# Enclosure_130x95_BPM-R.net
KiCad netlist of a schematic drawn in EAGLE
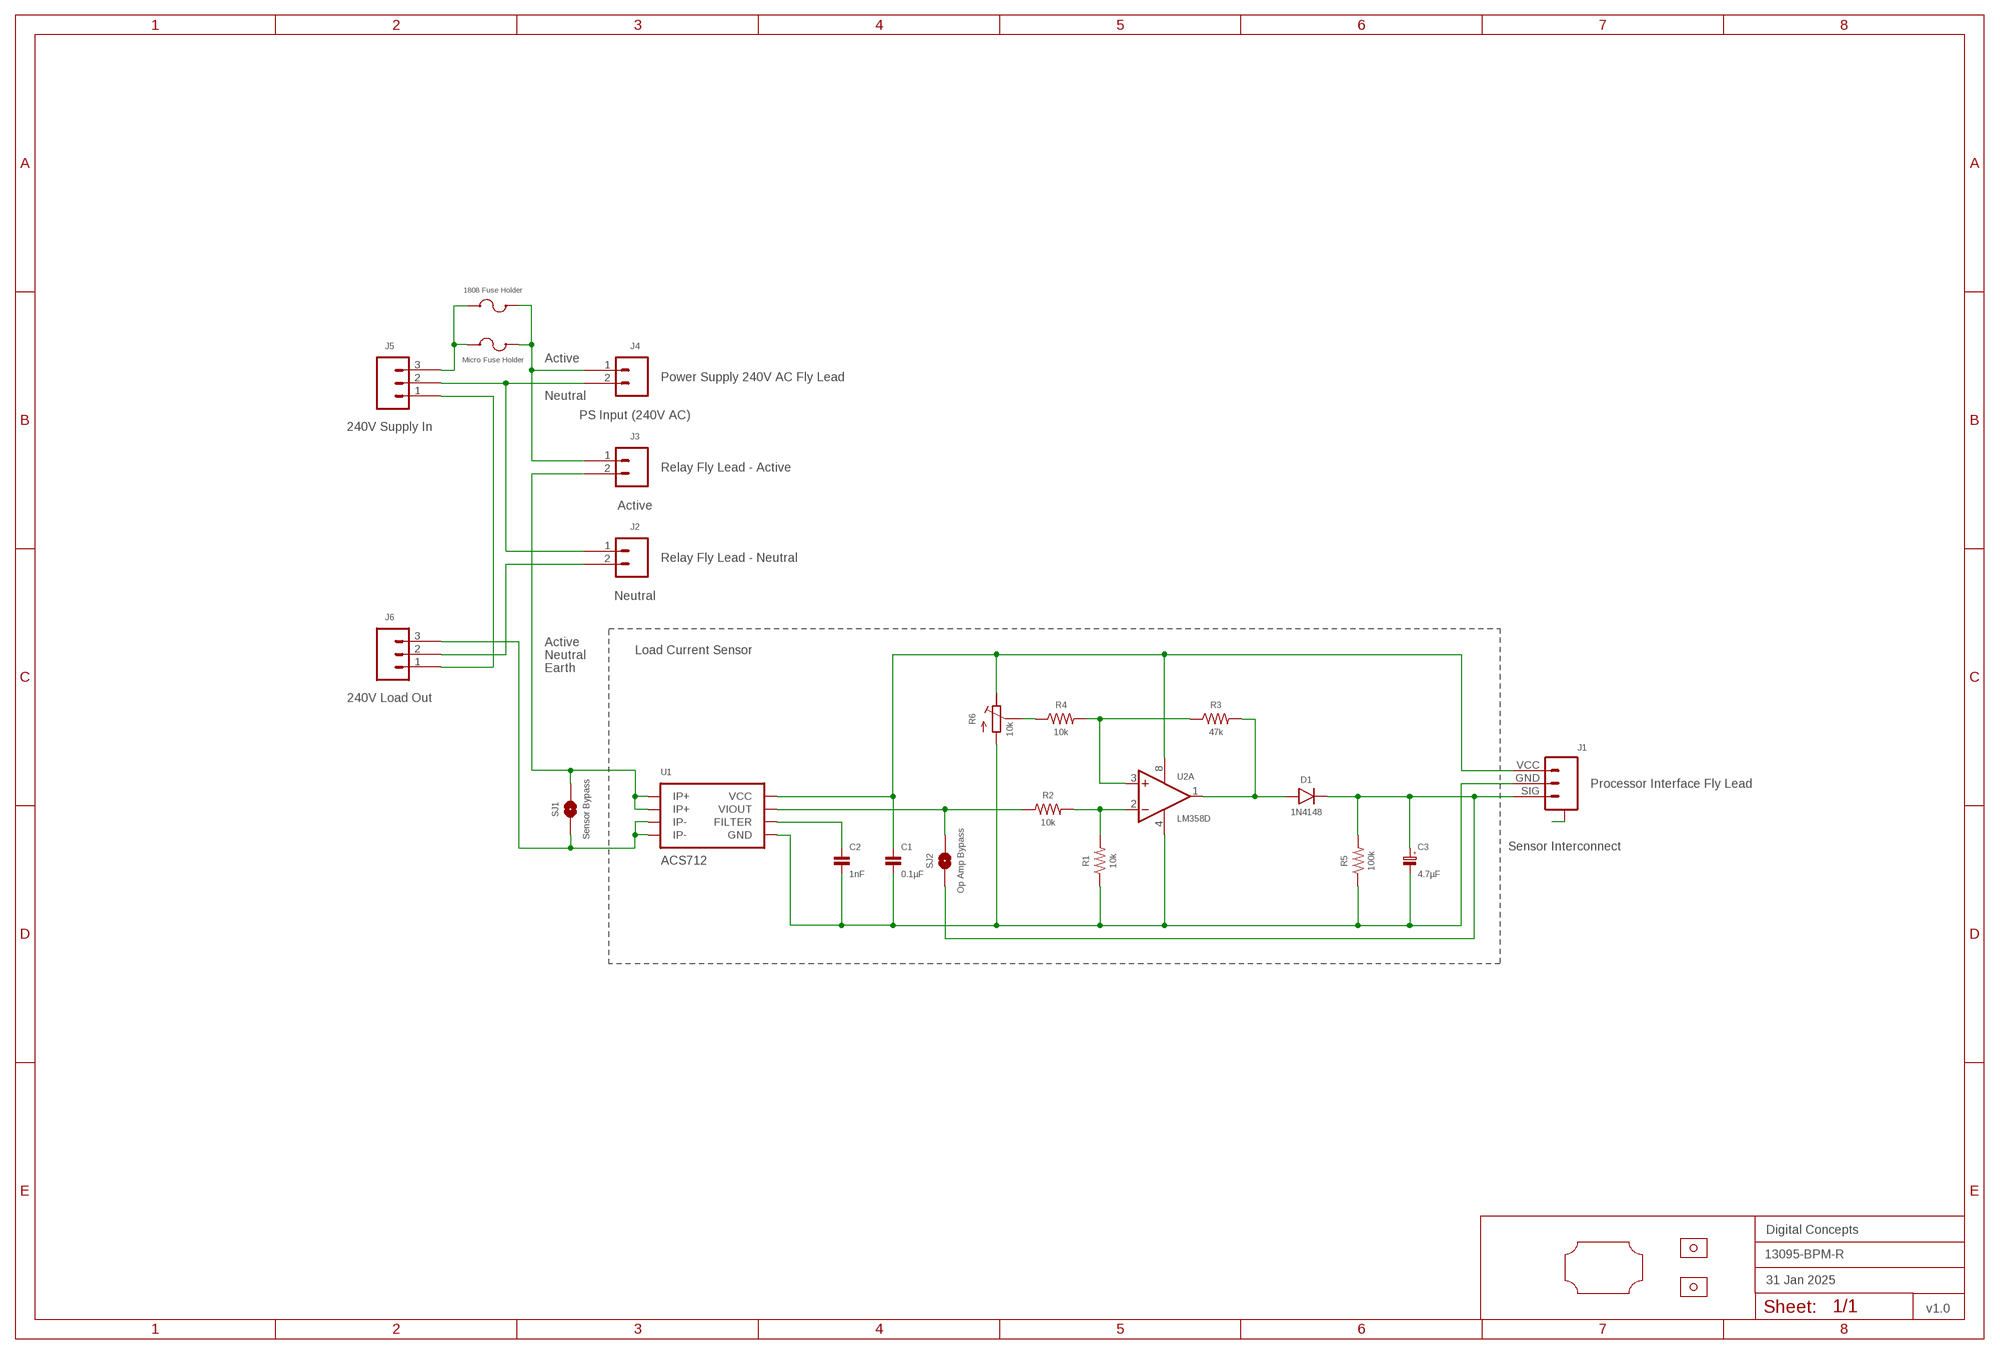
[diagram p0: schematic, sheet 1]

(export (version "E")
  (design (tool "Eeschema 10.0.6"))
  (components
    (comp (ref "C1")
      (value "0.1µF")
      (footprint "eagle-import:C0805")
      (libsource (lib "eagle-import") (part "CAPACITOR-0805"))
    )
    (comp (ref "C2")
      (value "1nF")
      (footprint "eagle-import:C0805")
      (libsource (lib "eagle-import") (part "CAPACITOR-0805"))
    )
    (comp (ref "C3")
      (value "4.7µF")
      (footprint "eagle-import:C1206-POLARISED")
      (libsource (lib "eagle-import") (part "CAPACITOR-1206-TANTALUM"))
    )
    (comp (ref "D1")
      (value "1N4148")
      (footprint "eagle-import:SOD-323")
      (libsource (lib "eagle-import") (part "DIODE-1N4148-SOD323"))
    )
    (comp (ref "F2")
      (value "1808 Fuse Holder")
      (footprint "eagle-import:FUSE-HOLDER-1808")
      (libsource (lib "eagle-import") (part "FUSE-HOLDER-1808"))
    )
    (comp (ref "J1")
      (value "Sensor Interconnect")
      (footprint "eagle-import:JST-SH1.0-3-HORIZONTAL-SIG")
      (libsource (lib "eagle-import") (part "JST-SH1.0-3-SMD-HORIZONTAL-SIG"))
    )
    (comp (ref "J2")
      (value "Neutral")
      (footprint "eagle-import:TERMINAL-SCREW-2P")
      (libsource (lib "eagle-import") (part "TERMINAL_SCREW_2P_VERTICAL"))
    )
    (comp (ref "J3")
      (value "Active")
      (footprint "eagle-import:TERMINAL-SCREW-2P")
      (libsource (lib "eagle-import") (part "TERMINAL_SCREW_2P_VERTICAL"))
    )
    (comp (ref "J4")
      (value "PS Input (240V AC)")
      (footprint "eagle-import:JST-XH2.4-2-HORIZONTAL")
      (libsource (lib "eagle-import") (part "JST-XH2.54-2-HORIZONTAL"))
    )
    (comp (ref "J5")
      (value "240V Supply In")
      (footprint "eagle-import:TERMINAL-SCREW-3P")
      (libsource (lib "eagle-import") (part "TERMINAL_SCREW_3P_VERTICAL"))
    )
    (comp (ref "J6")
      (value "240V Load Out")
      (footprint "eagle-import:TERMINAL-SCREW-3P")
      (libsource (lib "eagle-import") (part "TERMINAL_SCREW_3P_VERTICAL"))
    )
    (comp (ref "R1")
      (value "10k")
      (footprint "eagle-import:R0805")
      (libsource (lib "eagle-import") (part "RESISTORR0805"))
    )
    (comp (ref "R2")
      (value "10k")
      (footprint "eagle-import:R0805")
      (libsource (lib "eagle-import") (part "RESISTORR0805"))
    )
    (comp (ref "R3")
      (value "47k")
      (footprint "eagle-import:R0805")
      (libsource (lib "eagle-import") (part "RESISTORR0805"))
    )
    (comp (ref "R4")
      (value "10k")
      (footprint "eagle-import:R0805")
      (libsource (lib "eagle-import") (part "RESISTORR0805"))
    )
    (comp (ref "R5")
      (value "100k")
      (footprint "eagle-import:R0805")
      (libsource (lib "eagle-import") (part "RESISTORR0805"))
    )
    (comp (ref "R6")
      (value "10k")
      (footprint "eagle-import:RTRIM3386P")
      (libsource (lib "eagle-import") (part "RESISTOR-TRIMM-3386P"))
    )
    (comp (ref "SJ1")
      (value "Sensor Bypass")
      (footprint "eagle-import:SJ")
      (libsource (lib "eagle-import") (part "SJ"))
    )
    (comp (ref "SJ2")
      (value "Op Amp Bypass")
      (footprint "eagle-import:SJ")
      (libsource (lib "eagle-import") (part "SJ"))
    )
    (comp (ref "U$1")
      (value "PCB-OUTLINE-130X95-MAX-RC-H3")
      (footprint "eagle-import:PROTO-130X95-OUTLINE-MAX-RC-H3")
      (libsource (lib "eagle-import") (part "PCB-OUTLINE-130X95-MAX-RC-H3"))
    )
    (comp (ref "U$2")
      (value "Micro Fuse Holder")
      (footprint "eagle-import:FUSE-HOLDER-MICRO")
      (libsource (lib "eagle-import") (part "FUSE-HOLDER"))
    )
    (comp (ref "U$4")
      (value "STRAIN-RELIEF-SADDLE")
      (footprint "eagle-import:STRAIN-RELIEF-SADDLE")
      (libsource (lib "eagle-import") (part "STRAIN-RELIEF-SADDLE"))
    )
    (comp (ref "U$5")
      (value "STRAIN-RELIEF-SADDLE")
      (footprint "eagle-import:STRAIN-RELIEF-SADDLE")
      (libsource (lib "eagle-import") (part "STRAIN-RELIEF-SADDLE"))
    )
    (comp (ref "U1")
      (value "ACS712")
      (footprint "eagle-import:SOP-8")
      (libsource (lib "eagle-import") (part "ACS712"))
    )
    (comp (ref "U2")
      (value "LM358D")
      (footprint "eagle-import:SOP-8")
      (libsource (lib "eagle-import") (part "LM358D"))
    )
  )
  (nets
    (net (code "1") (name "Net-(C3-+)") (class "Default")
      (node (ref "C3") (pin "1") (pinfunction "+_1") (pintype "passive"))
      (node (ref "D1") (pin "C") (pinfunction "1_C") (pintype "bidirectional"))
      (node (ref "J1") (pin "SIG") (pinfunction "1_SIG") (pintype "passive"))
      (node (ref "R5") (pin "2") (pinfunction "2_2") (pintype "passive"))
      (node (ref "SJ2") (pin "1") (pinfunction "1_1") (pintype "passive"))
    )
    (net (code "2") (name "Net-(C3--)") (class "Default")
      (node (ref "C1") (pin "2") (pinfunction "2_2") (pintype "passive"))
      (node (ref "C2") (pin "2") (pinfunction "2_2") (pintype "passive"))
      (node (ref "C3") (pin "2") (pinfunction "-_2") (pintype "passive"))
      (node (ref "J1") (pin "GND") (pinfunction "2_GND") (pintype "passive"))
      (node (ref "R1") (pin "1") (pinfunction "1_1") (pintype "passive"))
      (node (ref "R5") (pin "1") (pinfunction "1_1") (pintype "passive"))
      (node (ref "R6") (pin "3") (pinfunction "A_3") (pintype "passive"))
      (node (ref "U1") (pin "5") (pinfunction "GND_5") (pintype "power_in"))
      (node (ref "U2") (pin "4") (pinfunction "V-_4") (pintype "power_in"))
    )
    (net (code "3") (name "Net-(D1-2)") (class "Default")
      (node (ref "D1") (pin "A") (pinfunction "2_A") (pintype "bidirectional"))
      (node (ref "R3") (pin "2") (pinfunction "2_2") (pintype "passive"))
      (node (ref "U2") (pin "1") (pinfunction "OUT_1") (pintype "output"))
    )
    (net (code "4") (name "Net-(F2-1)") (class "Default")
      (node (ref "F2") (pin "P$1") (pinfunction "1_P$1") (pintype "passive"))
      (node (ref "J5") (pin "3") (pinfunction "3_3") (pintype "passive"))
      (node (ref "U$2") (pin "P$1") (pinfunction "1_P$1") (pintype "passive"))
      (node (ref "U$2") (pin "P$2") (pinfunction "1_P$2") (pintype "passive"))
    )
    (net (code "5") (name "Net-(F2-2)") (class "Default")
      (node (ref "F2") (pin "P$2") (pinfunction "2_P$2") (pintype "passive"))
      (node (ref "J3") (pin "1") (pinfunction "1_1") (pintype "passive"))
      (node (ref "J4") (pin "1") (pinfunction "1_1") (pintype "passive"))
      (node (ref "U$2") (pin "P$3") (pinfunction "2_P$3") (pintype "passive"))
      (node (ref "U$2") (pin "P$4") (pinfunction "2_P$4") (pintype "passive"))
    )
    (net (code "6") (name "Net-(J1-3)") (class "Default")
      (node (ref "C1") (pin "1") (pinfunction "1_1") (pintype "passive"))
      (node (ref "J1") (pin "VCC") (pinfunction "3_VCC") (pintype "passive"))
      (node (ref "R6") (pin "1") (pinfunction "E_1") (pintype "passive"))
      (node (ref "U1") (pin "8") (pinfunction "VCC_8") (pintype "power_in"))
      (node (ref "U2") (pin "8") (pinfunction "V+_8") (pintype "power_in"))
    )
    (net (code "7") (name "Net-(J1-A-PadA@1)") (class "Default")
      (node (ref "J1") (pin "A@1") (pinfunction "A_A@1") (pintype "power_in"))
      (node (ref "J1") (pin "A@3") (pinfunction "A_A@3") (pintype "power_in"))
    )
    (net (code "8") (name "Net-(J2-Pad1)") (class "Default")
      (node (ref "J2") (pin "1") (pinfunction "1_1") (pintype "passive"))
      (node (ref "J4") (pin "2") (pinfunction "2_2") (pintype "passive"))
      (node (ref "J5") (pin "2") (pinfunction "2_2") (pintype "passive"))
    )
    (net (code "9") (name "Net-(J2-Pad2)") (class "Default")
      (node (ref "J2") (pin "2") (pinfunction "2_2") (pintype "passive"))
      (node (ref "J6") (pin "2") (pinfunction "2_2") (pintype "passive"))
    )
    (net (code "10") (name "Net-(J3-Pad2)") (class "Default")
      (node (ref "J3") (pin "2") (pinfunction "2_2") (pintype "passive"))
      (node (ref "SJ1") (pin "2") (pinfunction "2_2") (pintype "passive"))
      (node (ref "U1") (pin "1") (pinfunction "IP+_1") (pintype "bidirectional"))
      (node (ref "U1") (pin "2") (pinfunction "IP+_2") (pintype "bidirectional"))
    )
    (net (code "11") (name "Net-(J5-Pad1)") (class "Default")
      (node (ref "J5") (pin "1") (pinfunction "1_1") (pintype "passive"))
      (node (ref "J6") (pin "1") (pinfunction "1_1") (pintype "passive"))
    )
    (net (code "12") (name "Net-(J6-Pad3)") (class "Default")
      (node (ref "J6") (pin "3") (pinfunction "3_3") (pintype "passive"))
      (node (ref "SJ1") (pin "1") (pinfunction "1_1") (pintype "passive"))
      (node (ref "U1") (pin "3") (pinfunction "IP-_3") (pintype "bidirectional"))
      (node (ref "U1") (pin "4") (pinfunction "IP-_4") (pintype "bidirectional"))
    )
    (net (code "13") (name "Net-(R6-S)") (class "Default")
      (node (ref "R4") (pin "1") (pinfunction "1_1") (pintype "passive"))
      (node (ref "R6") (pin "2") (pinfunction "S_2") (pintype "passive"))
    )
    (net (code "14") (name "Net-(U1-FILTER)") (class "Default")
      (node (ref "C2") (pin "1") (pinfunction "1_1") (pintype "passive"))
      (node (ref "U1") (pin "6") (pinfunction "FILTER_6") (pintype "bidirectional"))
    )
    (net (code "15") (name "Net-(U1-VIOUT)") (class "Default")
      (node (ref "R2") (pin "1") (pinfunction "1_1") (pintype "passive"))
      (node (ref "SJ2") (pin "2") (pinfunction "2_2") (pintype "passive"))
      (node (ref "U1") (pin "7") (pinfunction "VIOUT_7") (pintype "bidirectional"))
    )
    (net (code "16") (name "Net-(U2A-+IN)") (class "Default")
      (node (ref "R3") (pin "1") (pinfunction "1_1") (pintype "passive"))
      (node (ref "R4") (pin "2") (pinfunction "2_2") (pintype "passive"))
      (node (ref "U2") (pin "3") (pinfunction "+IN_3") (pintype "input"))
    )
    (net (code "17") (name "Net-(U2A--IN)") (class "Default")
      (node (ref "R1") (pin "2") (pinfunction "2_2") (pintype "passive"))
      (node (ref "R2") (pin "2") (pinfunction "2_2") (pintype "passive"))
      (node (ref "U2") (pin "2") (pinfunction "-IN_2") (pintype "input"))
    )
  )
)
